# rockchip-mics.net
KiCad netlist of a schematic drawn in EAGLE
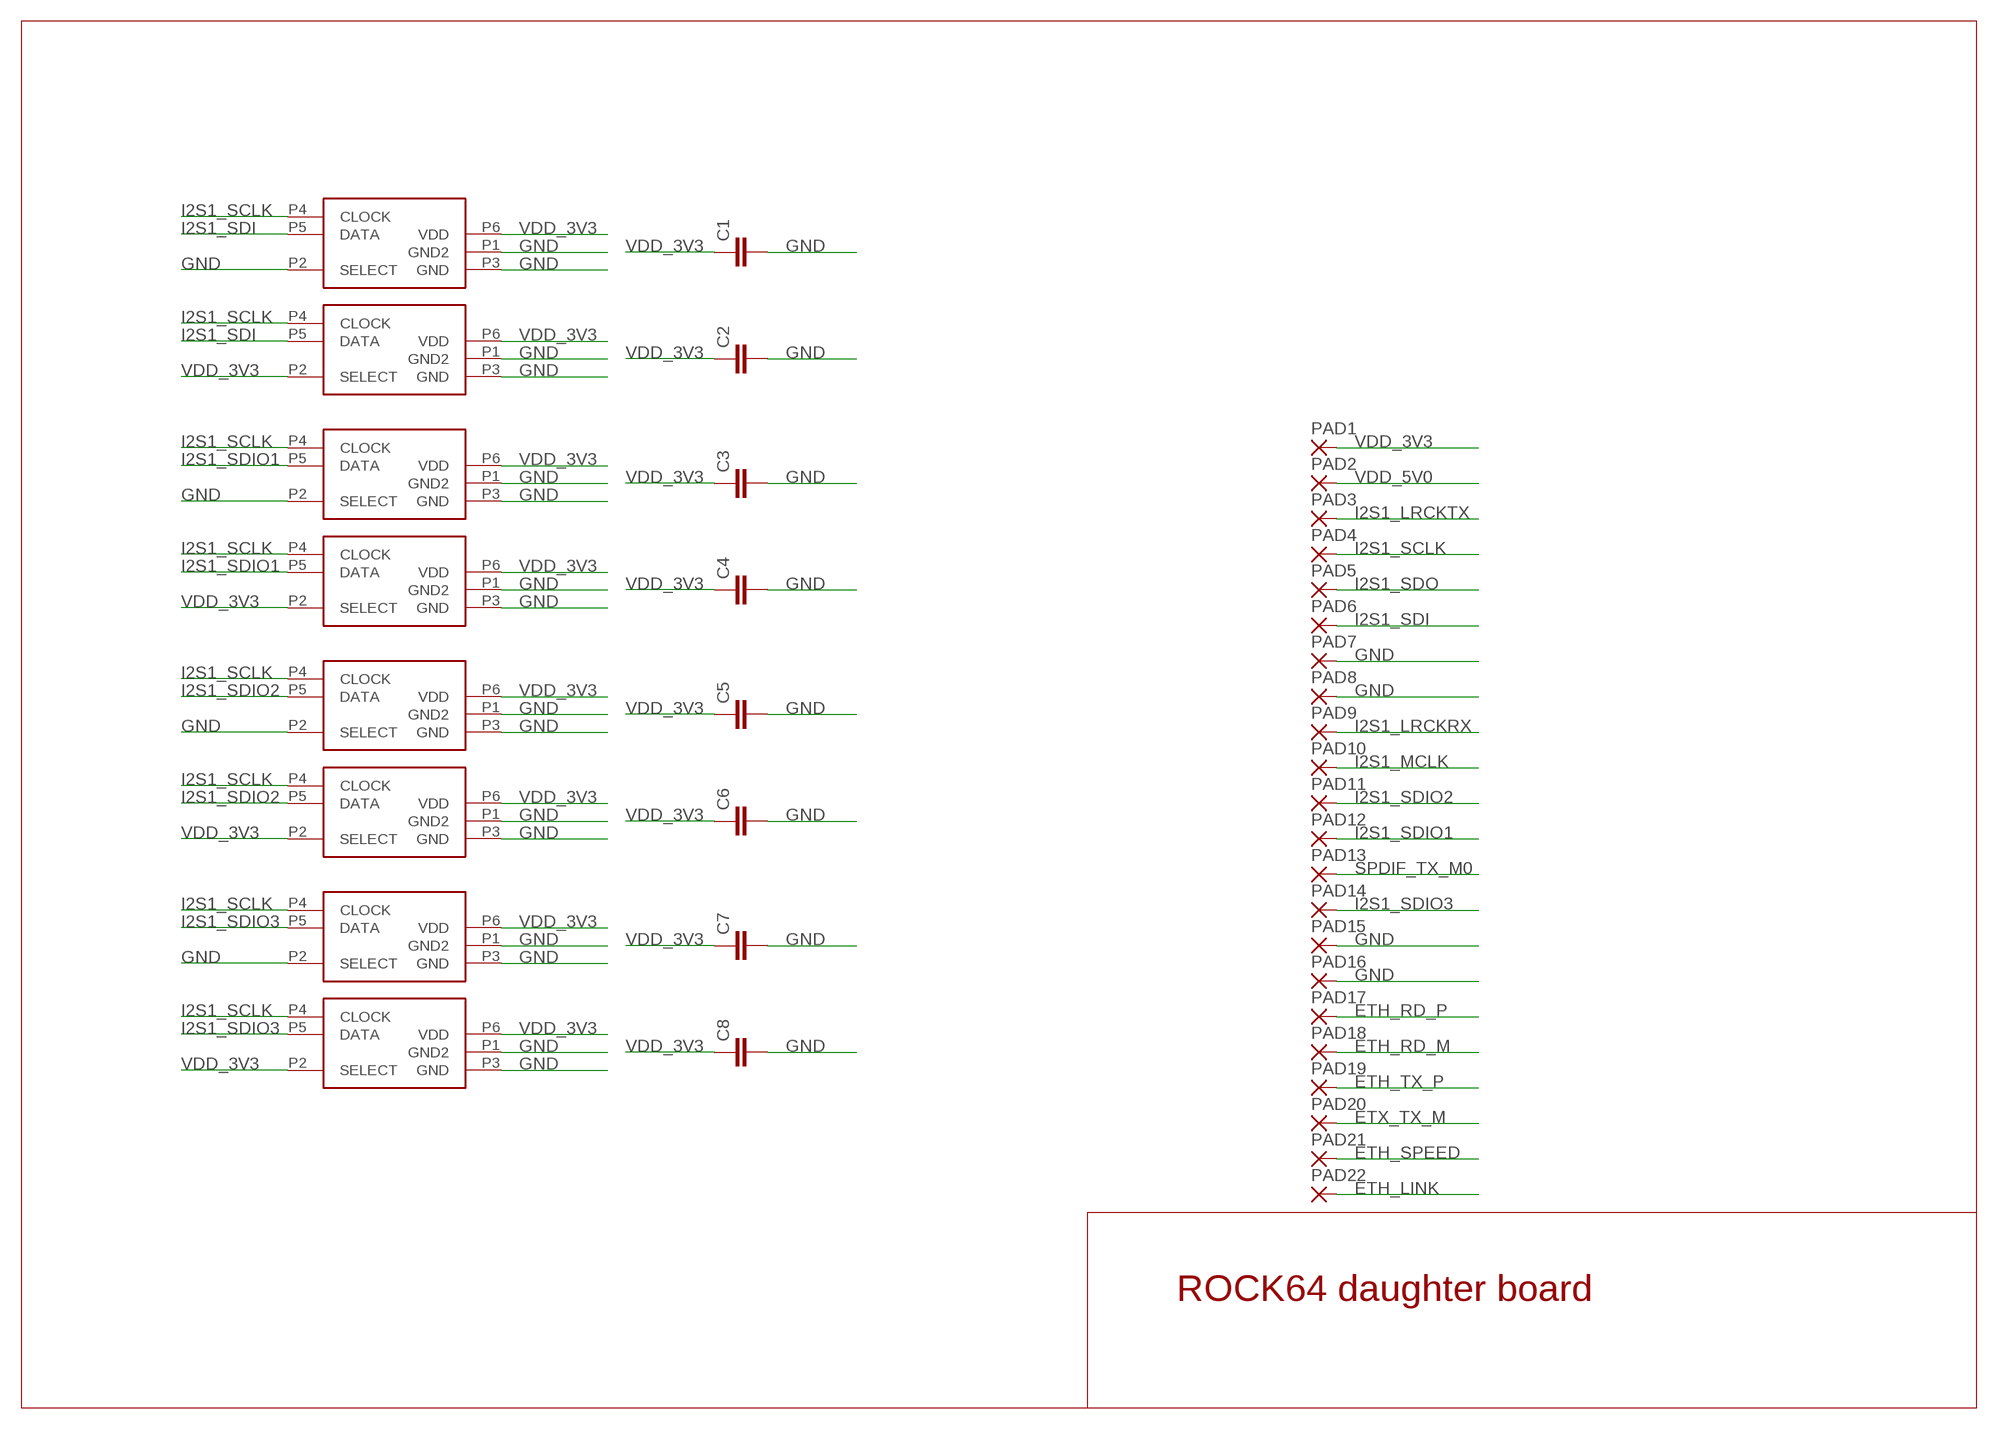
[diagram p0: schematic, sheet 1]

(export (version "E")
  (design (tool "Eeschema 10.0.6"))
  (components
    (comp (ref "C1")
      (value "C-EUC1206")
      (footprint "eagle-import:C1206")
      (libsource (lib "eagle-import") (part "C-EUC1206"))
    )
    (comp (ref "C2")
      (value "C-EUC1206")
      (footprint "eagle-import:C1206")
      (libsource (lib "eagle-import") (part "C-EUC1206"))
    )
    (comp (ref "C3")
      (value "C-EUC1206")
      (footprint "eagle-import:C1206")
      (libsource (lib "eagle-import") (part "C-EUC1206"))
    )
    (comp (ref "C4")
      (value "C-EUC1206")
      (footprint "eagle-import:C1206")
      (libsource (lib "eagle-import") (part "C-EUC1206"))
    )
    (comp (ref "C5")
      (value "C-EUC1206")
      (footprint "eagle-import:C1206")
      (libsource (lib "eagle-import") (part "C-EUC1206"))
    )
    (comp (ref "C6")
      (value "C-EUC1206")
      (footprint "eagle-import:C1206")
      (libsource (lib "eagle-import") (part "C-EUC1206"))
    )
    (comp (ref "C7")
      (value "C-EUC1206")
      (footprint "eagle-import:C1206")
      (libsource (lib "eagle-import") (part "C-EUC1206"))
    )
    (comp (ref "C8")
      (value "C-EUC1206")
      (footprint "eagle-import:C1206")
      (libsource (lib "eagle-import") (part "C-EUC1206"))
    )
    (comp (ref "PAD1")
      (value "1,6/0,8")
      (footprint "eagle-import:1,6_0,8")
      (libsource (lib "eagle-import") (part "1,6/0,8"))
    )
    (comp (ref "PAD2")
      (value "1,6/0,8")
      (footprint "eagle-import:1,6_0,8")
      (libsource (lib "eagle-import") (part "1,6/0,8"))
    )
    (comp (ref "PAD3")
      (value "1,6/0,8")
      (footprint "eagle-import:1,6_0,8")
      (libsource (lib "eagle-import") (part "1,6/0,8"))
    )
    (comp (ref "PAD4")
      (value "1,6/0,8")
      (footprint "eagle-import:1,6_0,8")
      (libsource (lib "eagle-import") (part "1,6/0,8"))
    )
    (comp (ref "PAD5")
      (value "1,6/0,8")
      (footprint "eagle-import:1,6_0,8")
      (libsource (lib "eagle-import") (part "1,6/0,8"))
    )
    (comp (ref "PAD6")
      (value "1,6/0,8")
      (footprint "eagle-import:1,6_0,8")
      (libsource (lib "eagle-import") (part "1,6/0,8"))
    )
    (comp (ref "PAD7")
      (value "1,6/0,8")
      (footprint "eagle-import:1,6_0,8")
      (libsource (lib "eagle-import") (part "1,6/0,8"))
    )
    (comp (ref "PAD8")
      (value "1,6/0,8")
      (footprint "eagle-import:1,6_0,8")
      (libsource (lib "eagle-import") (part "1,6/0,8"))
    )
    (comp (ref "PAD9")
      (value "1,6/0,8")
      (footprint "eagle-import:1,6_0,8")
      (libsource (lib "eagle-import") (part "1,6/0,8"))
    )
    (comp (ref "PAD10")
      (value "1,6/0,8")
      (footprint "eagle-import:1,6_0,8")
      (libsource (lib "eagle-import") (part "1,6/0,8"))
    )
    (comp (ref "PAD11")
      (value "1,6/0,8")
      (footprint "eagle-import:1,6_0,8")
      (libsource (lib "eagle-import") (part "1,6/0,8"))
    )
    (comp (ref "PAD12")
      (value "1,6/0,8")
      (footprint "eagle-import:1,6_0,8")
      (libsource (lib "eagle-import") (part "1,6/0,8"))
    )
    (comp (ref "PAD13")
      (value "1,6/0,8")
      (footprint "eagle-import:1,6_0,8")
      (libsource (lib "eagle-import") (part "1,6/0,8"))
    )
    (comp (ref "PAD14")
      (value "1,6/0,8")
      (footprint "eagle-import:1,6_0,8")
      (libsource (lib "eagle-import") (part "1,6/0,8"))
    )
    (comp (ref "PAD15")
      (value "1,6/0,8")
      (footprint "eagle-import:1,6_0,8")
      (libsource (lib "eagle-import") (part "1,6/0,8"))
    )
    (comp (ref "PAD16")
      (value "1,6/0,8")
      (footprint "eagle-import:1,6_0,8")
      (libsource (lib "eagle-import") (part "1,6/0,8"))
    )
    (comp (ref "PAD17")
      (value "1,6/0,8")
      (footprint "eagle-import:1,6_0,8")
      (libsource (lib "eagle-import") (part "1,6/0,8"))
    )
    (comp (ref "PAD18")
      (value "1,6/0,8")
      (footprint "eagle-import:1,6_0,8")
      (libsource (lib "eagle-import") (part "1,6/0,8"))
    )
    (comp (ref "PAD19")
      (value "1,6/0,8")
      (footprint "eagle-import:1,6_0,8")
      (libsource (lib "eagle-import") (part "1,6/0,8"))
    )
    (comp (ref "PAD20")
      (value "1,6/0,8")
      (footprint "eagle-import:1,6_0,8")
      (libsource (lib "eagle-import") (part "1,6/0,8"))
    )
    (comp (ref "PAD21")
      (value "1,6/0,8")
      (footprint "eagle-import:1,6_0,8")
      (libsource (lib "eagle-import") (part "1,6/0,8"))
    )
    (comp (ref "PAD22")
      (value "1,6/0,8")
      (footprint "eagle-import:1,6_0,8")
      (libsource (lib "eagle-import") (part "1,6/0,8"))
    )
    (comp (ref "U$1")
      (value "SPM0423SMD")
      (footprint "eagle-import:SPM0423")
      (libsource (lib "eagle-import") (part "SPM0423SMD"))
    )
    (comp (ref "U$2")
      (value "SPM0423SMD")
      (footprint "eagle-import:SPM0423")
      (libsource (lib "eagle-import") (part "SPM0423SMD"))
    )
    (comp (ref "U$3")
      (value "SPM0423SMD")
      (footprint "eagle-import:SPM0423")
      (libsource (lib "eagle-import") (part "SPM0423SMD"))
    )
    (comp (ref "U$4")
      (value "SPM0423SMD")
      (footprint "eagle-import:SPM0423")
      (libsource (lib "eagle-import") (part "SPM0423SMD"))
    )
    (comp (ref "U$5")
      (value "SPM0423SMD")
      (footprint "eagle-import:SPM0423")
      (libsource (lib "eagle-import") (part "SPM0423SMD"))
    )
    (comp (ref "U$6")
      (value "SPM0423SMD")
      (footprint "eagle-import:SPM0423")
      (libsource (lib "eagle-import") (part "SPM0423SMD"))
    )
    (comp (ref "U$7")
      (value "SPM0423SMD")
      (footprint "eagle-import:SPM0423")
      (libsource (lib "eagle-import") (part "SPM0423SMD"))
    )
    (comp (ref "U$8")
      (value "SPM0423SMD")
      (footprint "eagle-import:SPM0423")
      (libsource (lib "eagle-import") (part "SPM0423SMD"))
    )
  )
  (nets
    (net (code "1") (name "/ETH_LINK") (class "Default")
      (node (ref "PAD22") (pin "1") (pinfunction "P_1") (pintype "passive"))
    )
    (net (code "2") (name "/ETH_RD_M") (class "Default")
      (node (ref "PAD18") (pin "1") (pinfunction "P_1") (pintype "passive"))
    )
    (net (code "3") (name "/ETH_RD_P") (class "Default")
      (node (ref "PAD17") (pin "1") (pinfunction "P_1") (pintype "passive"))
    )
    (net (code "4") (name "/ETH_SPEED") (class "Default")
      (node (ref "PAD21") (pin "1") (pinfunction "P_1") (pintype "passive"))
    )
    (net (code "5") (name "/ETH_TX_P") (class "Default")
      (node (ref "PAD19") (pin "1") (pinfunction "P_1") (pintype "passive"))
    )
    (net (code "6") (name "/ETX_TX_M") (class "Default")
      (node (ref "PAD20") (pin "1") (pinfunction "P_1") (pintype "passive"))
    )
    (net (code "7") (name "/GND") (class "Default")
      (node (ref "C1") (pin "2") (pinfunction "2_2") (pintype "passive"))
      (node (ref "C2") (pin "2") (pinfunction "2_2") (pintype "passive"))
      (node (ref "C3") (pin "2") (pinfunction "2_2") (pintype "passive"))
      (node (ref "C4") (pin "2") (pinfunction "2_2") (pintype "passive"))
      (node (ref "C5") (pin "2") (pinfunction "2_2") (pintype "passive"))
      (node (ref "C6") (pin "2") (pinfunction "2_2") (pintype "passive"))
      (node (ref "C7") (pin "2") (pinfunction "2_2") (pintype "passive"))
      (node (ref "C8") (pin "2") (pinfunction "2_2") (pintype "passive"))
      (node (ref "PAD15") (pin "1") (pinfunction "P_1") (pintype "passive"))
      (node (ref "PAD16") (pin "1") (pinfunction "P_1") (pintype "passive"))
      (node (ref "PAD7") (pin "1") (pinfunction "P_1") (pintype "passive"))
      (node (ref "PAD8") (pin "1") (pinfunction "P_1") (pintype "passive"))
      (node (ref "U$1") (pin "P1") (pinfunction "GND2_P1") (pintype "power_in"))
      (node (ref "U$1") (pin "P2") (pinfunction "SELECT_P2") (pintype "input"))
      (node (ref "U$1") (pin "P3") (pinfunction "GND_P3") (pintype "power_in"))
      (node (ref "U$2") (pin "P1") (pinfunction "GND2_P1") (pintype "power_in"))
      (node (ref "U$2") (pin "P3") (pinfunction "GND_P3") (pintype "power_in"))
      (node (ref "U$3") (pin "P1") (pinfunction "GND2_P1") (pintype "power_in"))
      (node (ref "U$3") (pin "P2") (pinfunction "SELECT_P2") (pintype "input"))
      (node (ref "U$3") (pin "P3") (pinfunction "GND_P3") (pintype "power_in"))
      (node (ref "U$4") (pin "P1") (pinfunction "GND2_P1") (pintype "power_in"))
      (node (ref "U$4") (pin "P3") (pinfunction "GND_P3") (pintype "power_in"))
      (node (ref "U$5") (pin "P1") (pinfunction "GND2_P1") (pintype "power_in"))
      (node (ref "U$5") (pin "P2") (pinfunction "SELECT_P2") (pintype "input"))
      (node (ref "U$5") (pin "P3") (pinfunction "GND_P3") (pintype "power_in"))
      (node (ref "U$6") (pin "P1") (pinfunction "GND2_P1") (pintype "power_in"))
      (node (ref "U$6") (pin "P3") (pinfunction "GND_P3") (pintype "power_in"))
      (node (ref "U$7") (pin "P1") (pinfunction "GND2_P1") (pintype "power_in"))
      (node (ref "U$7") (pin "P2") (pinfunction "SELECT_P2") (pintype "input"))
      (node (ref "U$7") (pin "P3") (pinfunction "GND_P3") (pintype "power_in"))
      (node (ref "U$8") (pin "P1") (pinfunction "GND2_P1") (pintype "power_in"))
      (node (ref "U$8") (pin "P3") (pinfunction "GND_P3") (pintype "power_in"))
    )
    (net (code "8") (name "/I2S1_LRCKRX") (class "Default")
      (node (ref "PAD9") (pin "1") (pinfunction "P_1") (pintype "passive"))
    )
    (net (code "9") (name "/I2S1_LRCKTX") (class "Default")
      (node (ref "PAD3") (pin "1") (pinfunction "P_1") (pintype "passive"))
    )
    (net (code "10") (name "/I2S1_MCLK") (class "Default")
      (node (ref "PAD10") (pin "1") (pinfunction "P_1") (pintype "passive"))
    )
    (net (code "11") (name "/I2S1_SCLK") (class "Default")
      (node (ref "PAD4") (pin "1") (pinfunction "P_1") (pintype "passive"))
      (node (ref "U$1") (pin "P4") (pinfunction "CLOCK_P4") (pintype "bidirectional"))
      (node (ref "U$2") (pin "P4") (pinfunction "CLOCK_P4") (pintype "bidirectional"))
      (node (ref "U$3") (pin "P4") (pinfunction "CLOCK_P4") (pintype "bidirectional"))
      (node (ref "U$4") (pin "P4") (pinfunction "CLOCK_P4") (pintype "bidirectional"))
      (node (ref "U$5") (pin "P4") (pinfunction "CLOCK_P4") (pintype "bidirectional"))
      (node (ref "U$6") (pin "P4") (pinfunction "CLOCK_P4") (pintype "bidirectional"))
      (node (ref "U$7") (pin "P4") (pinfunction "CLOCK_P4") (pintype "bidirectional"))
      (node (ref "U$8") (pin "P4") (pinfunction "CLOCK_P4") (pintype "bidirectional"))
    )
    (net (code "12") (name "/I2S1_SDI") (class "Default")
      (node (ref "PAD6") (pin "1") (pinfunction "P_1") (pintype "passive"))
      (node (ref "U$1") (pin "P5") (pinfunction "DATA_P5") (pintype "bidirectional"))
      (node (ref "U$2") (pin "P5") (pinfunction "DATA_P5") (pintype "bidirectional"))
    )
    (net (code "13") (name "/I2S1_SDIO1") (class "Default")
      (node (ref "PAD12") (pin "1") (pinfunction "P_1") (pintype "passive"))
      (node (ref "U$3") (pin "P5") (pinfunction "DATA_P5") (pintype "bidirectional"))
      (node (ref "U$4") (pin "P5") (pinfunction "DATA_P5") (pintype "bidirectional"))
    )
    (net (code "14") (name "/I2S1_SDIO2") (class "Default")
      (node (ref "PAD11") (pin "1") (pinfunction "P_1") (pintype "passive"))
      (node (ref "U$5") (pin "P5") (pinfunction "DATA_P5") (pintype "bidirectional"))
      (node (ref "U$6") (pin "P5") (pinfunction "DATA_P5") (pintype "bidirectional"))
    )
    (net (code "15") (name "/I2S1_SDIO3") (class "Default")
      (node (ref "PAD14") (pin "1") (pinfunction "P_1") (pintype "passive"))
      (node (ref "U$7") (pin "P5") (pinfunction "DATA_P5") (pintype "bidirectional"))
      (node (ref "U$8") (pin "P5") (pinfunction "DATA_P5") (pintype "bidirectional"))
    )
    (net (code "16") (name "/I2S1_SDO") (class "Default")
      (node (ref "PAD5") (pin "1") (pinfunction "P_1") (pintype "passive"))
    )
    (net (code "17") (name "/SPDIF_TX_M0") (class "Default")
      (node (ref "PAD13") (pin "1") (pinfunction "P_1") (pintype "passive"))
    )
    (net (code "18") (name "/VDD_3V3") (class "Default")
      (node (ref "C1") (pin "1") (pinfunction "1_1") (pintype "passive"))
      (node (ref "C2") (pin "1") (pinfunction "1_1") (pintype "passive"))
      (node (ref "C3") (pin "1") (pinfunction "1_1") (pintype "passive"))
      (node (ref "C4") (pin "1") (pinfunction "1_1") (pintype "passive"))
      (node (ref "C5") (pin "1") (pinfunction "1_1") (pintype "passive"))
      (node (ref "C6") (pin "1") (pinfunction "1_1") (pintype "passive"))
      (node (ref "C7") (pin "1") (pinfunction "1_1") (pintype "passive"))
      (node (ref "C8") (pin "1") (pinfunction "1_1") (pintype "passive"))
      (node (ref "PAD1") (pin "1") (pinfunction "P_1") (pintype "passive"))
      (node (ref "U$1") (pin "P6") (pinfunction "VDD_P6") (pintype "power_in"))
      (node (ref "U$2") (pin "P2") (pinfunction "SELECT_P2") (pintype "input"))
      (node (ref "U$2") (pin "P6") (pinfunction "VDD_P6") (pintype "power_in"))
      (node (ref "U$3") (pin "P6") (pinfunction "VDD_P6") (pintype "power_in"))
      (node (ref "U$4") (pin "P2") (pinfunction "SELECT_P2") (pintype "input"))
      (node (ref "U$4") (pin "P6") (pinfunction "VDD_P6") (pintype "power_in"))
      (node (ref "U$5") (pin "P6") (pinfunction "VDD_P6") (pintype "power_in"))
      (node (ref "U$6") (pin "P2") (pinfunction "SELECT_P2") (pintype "input"))
      (node (ref "U$6") (pin "P6") (pinfunction "VDD_P6") (pintype "power_in"))
      (node (ref "U$7") (pin "P6") (pinfunction "VDD_P6") (pintype "power_in"))
      (node (ref "U$8") (pin "P2") (pinfunction "SELECT_P2") (pintype "input"))
      (node (ref "U$8") (pin "P6") (pinfunction "VDD_P6") (pintype "power_in"))
    )
    (net (code "19") (name "/VDD_5V0") (class "Default")
      (node (ref "PAD2") (pin "1") (pinfunction "P_1") (pintype "passive"))
    )
  )
)
